# RGBM-02.net
KiCad netlist of a schematic drawn in Altium Designer
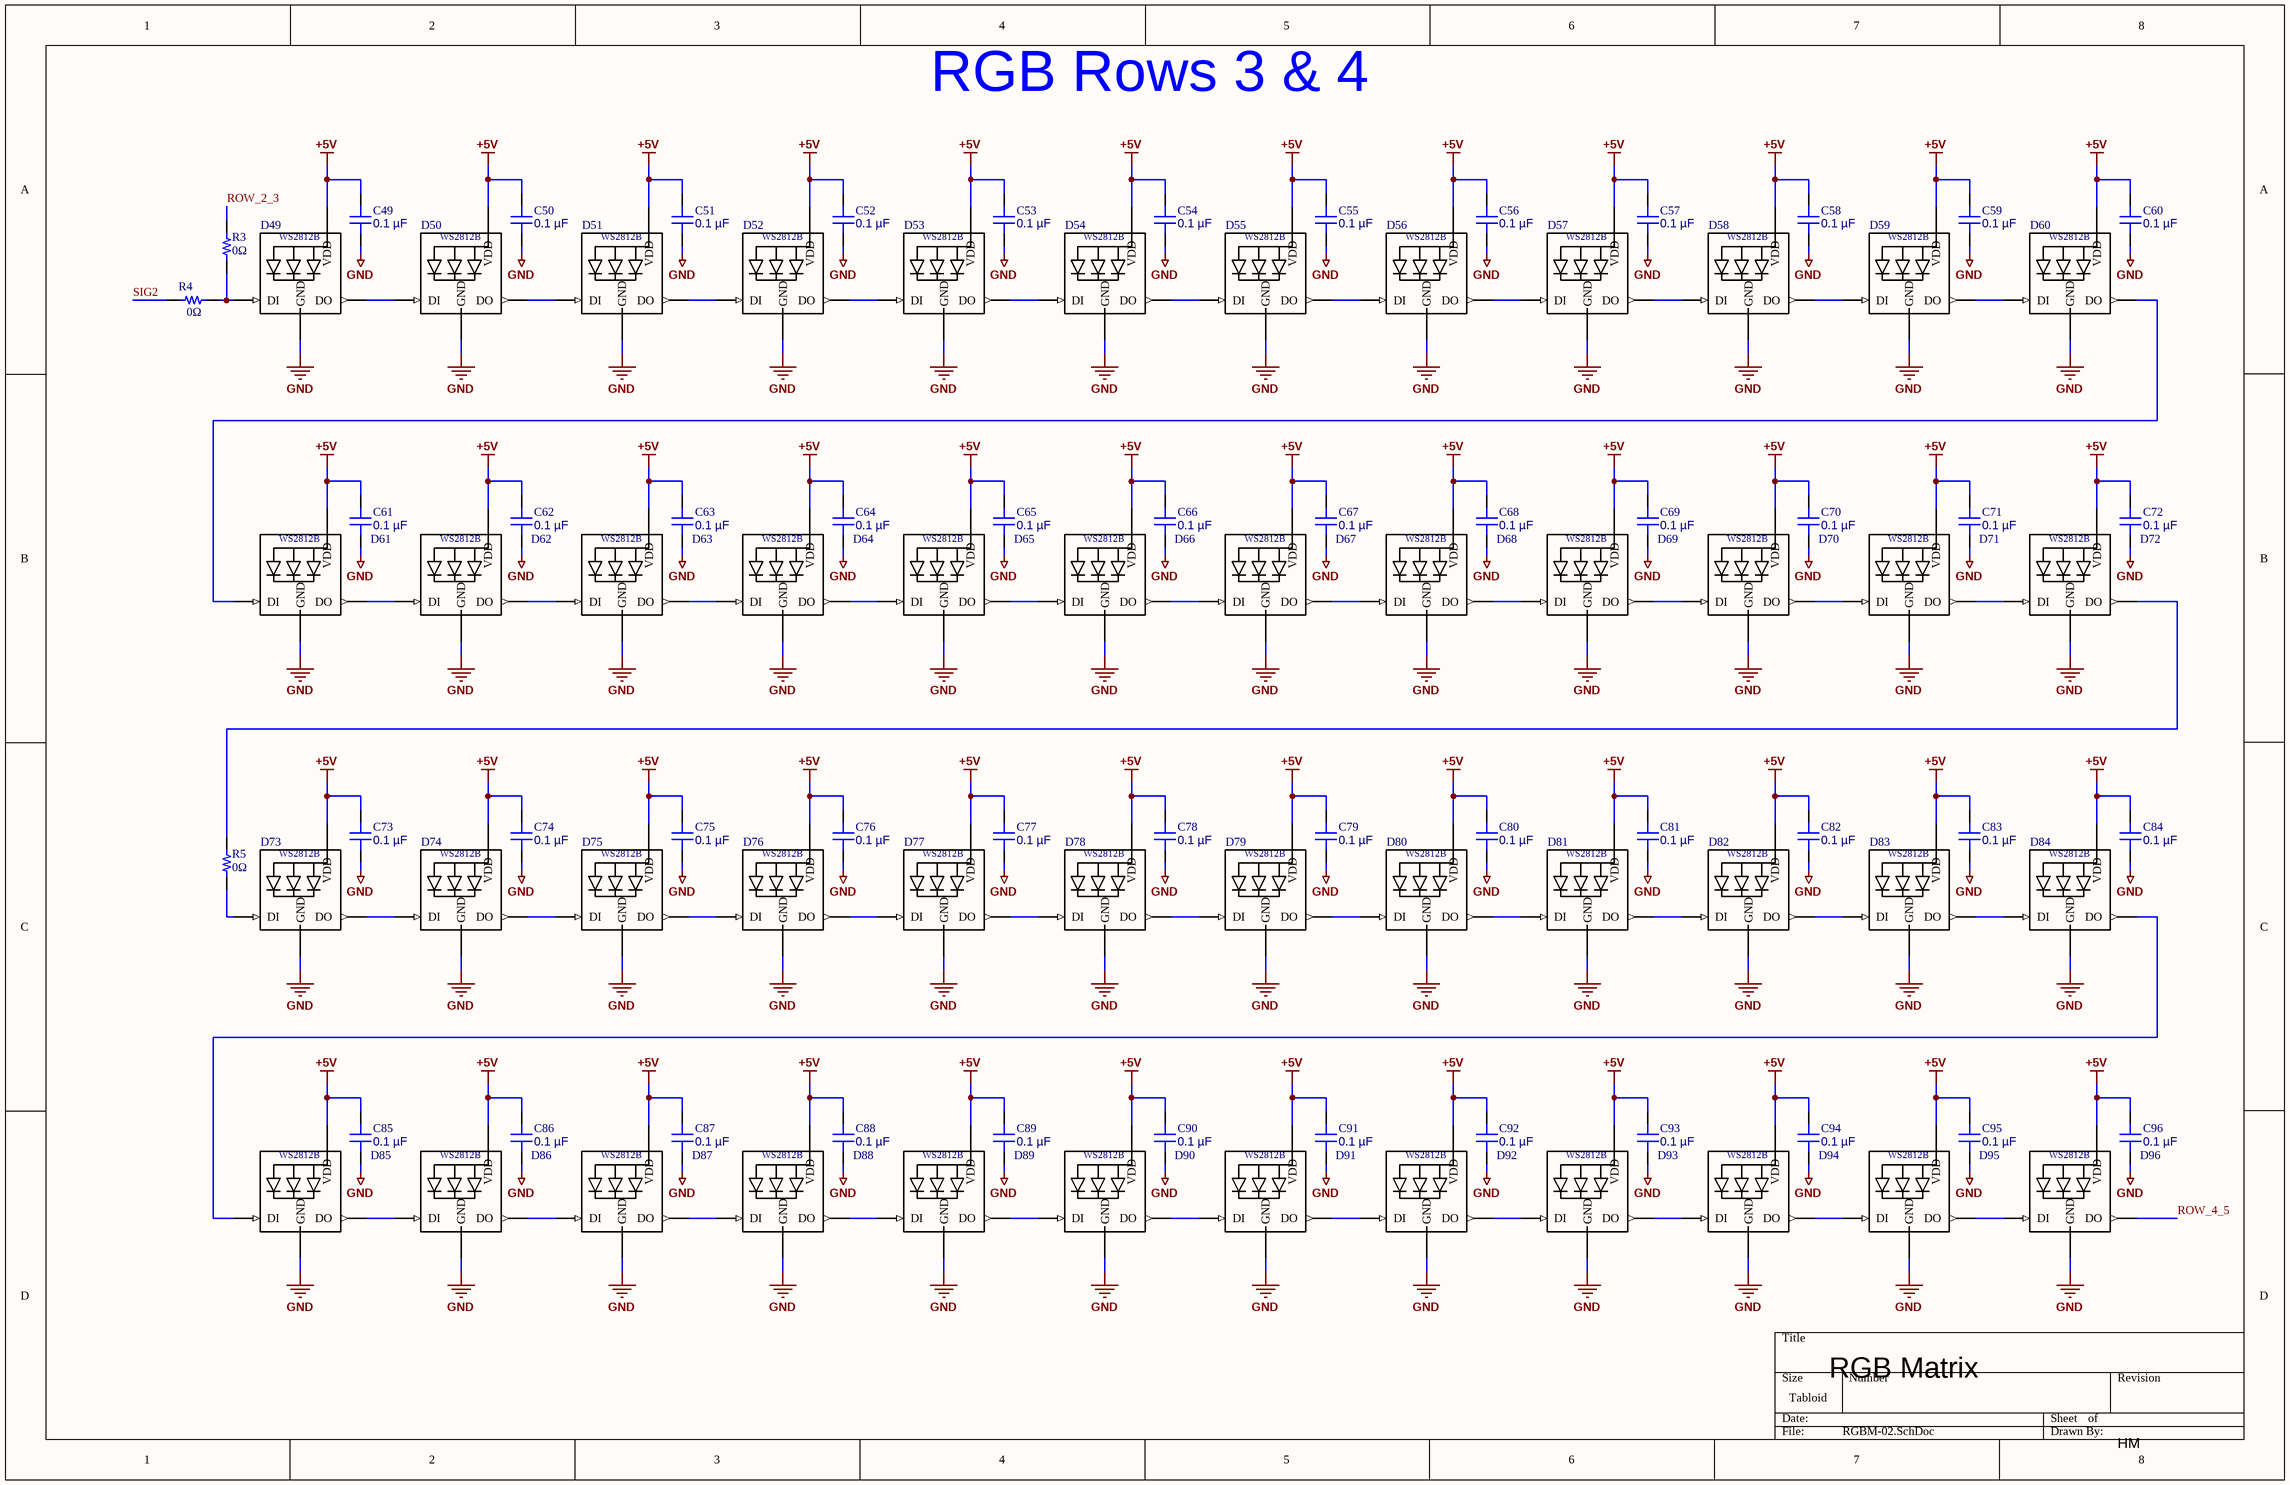
[diagram p0: RGBM-02.SchDoc]

(export (version "E")
  (design (tool "Eeschema 10.0.6"))
  (components
    (comp (ref "C49")
      (value "0.1 µF")
      (footprint "CAP 0603_1608")
      (description "CAP CER 0.1UF 50V X7R 0603")
      (fields
        (field (name "PART NUMBER") "C0603C104K5RAC7411")
        (field (name "CAPACITANCE") "0.1 µF")
        (field (name "MANUFACTURER") "KEMET")
      )
      (libsource (lib "Celestial Altium Library - altium_library") (part "Capacitor"))
    )
    (comp (ref "C50")
      (value "0.1 µF")
      (footprint "CAP 0603_1608")
      (description "CAP CER 0.1UF 50V X7R 0603")
      (fields
        (field (name "PART NUMBER") "C0603C104K5RAC7411")
        (field (name "CAPACITANCE") "0.1 µF")
        (field (name "MANUFACTURER") "KEMET")
      )
      (libsource (lib "Celestial Altium Library - altium_library") (part "Capacitor"))
    )
    (comp (ref "C51")
      (value "0.1 µF")
      (footprint "CAP 0603_1608")
      (description "CAP CER 0.1UF 50V X7R 0603")
      (fields
        (field (name "PART NUMBER") "C0603C104K5RAC7411")
        (field (name "CAPACITANCE") "0.1 µF")
        (field (name "MANUFACTURER") "KEMET")
      )
      (libsource (lib "Celestial Altium Library - altium_library") (part "Capacitor"))
    )
    (comp (ref "C52")
      (value "0.1 µF")
      (footprint "CAP 0603_1608")
      (description "CAP CER 0.1UF 50V X7R 0603")
      (fields
        (field (name "PART NUMBER") "C0603C104K5RAC7411")
        (field (name "CAPACITANCE") "0.1 µF")
        (field (name "MANUFACTURER") "KEMET")
      )
      (libsource (lib "Celestial Altium Library - altium_library") (part "Capacitor"))
    )
    (comp (ref "C53")
      (value "0.1 µF")
      (footprint "CAP 0603_1608")
      (description "CAP CER 0.1UF 50V X7R 0603")
      (fields
        (field (name "PART NUMBER") "C0603C104K5RAC7411")
        (field (name "CAPACITANCE") "0.1 µF")
        (field (name "MANUFACTURER") "KEMET")
      )
      (libsource (lib "Celestial Altium Library - altium_library") (part "Capacitor"))
    )
    (comp (ref "C54")
      (value "0.1 µF")
      (footprint "CAP 0603_1608")
      (description "CAP CER 0.1UF 50V X7R 0603")
      (fields
        (field (name "PART NUMBER") "C0603C104K5RAC7411")
        (field (name "CAPACITANCE") "0.1 µF")
        (field (name "MANUFACTURER") "KEMET")
      )
      (libsource (lib "Celestial Altium Library - altium_library") (part "Capacitor"))
    )
    (comp (ref "C55")
      (value "0.1 µF")
      (footprint "CAP 0603_1608")
      (description "CAP CER 0.1UF 50V X7R 0603")
      (fields
        (field (name "PART NUMBER") "C0603C104K5RAC7411")
        (field (name "CAPACITANCE") "0.1 µF")
        (field (name "MANUFACTURER") "KEMET")
      )
      (libsource (lib "Celestial Altium Library - altium_library") (part "Capacitor"))
    )
    (comp (ref "C56")
      (value "0.1 µF")
      (footprint "CAP 0603_1608")
      (description "CAP CER 0.1UF 50V X7R 0603")
      (fields
        (field (name "PART NUMBER") "C0603C104K5RAC7411")
        (field (name "CAPACITANCE") "0.1 µF")
        (field (name "MANUFACTURER") "KEMET")
      )
      (libsource (lib "Celestial Altium Library - altium_library") (part "Capacitor"))
    )
    (comp (ref "C57")
      (value "0.1 µF")
      (footprint "CAP 0603_1608")
      (description "CAP CER 0.1UF 50V X7R 0603")
      (fields
        (field (name "PART NUMBER") "C0603C104K5RAC7411")
        (field (name "CAPACITANCE") "0.1 µF")
        (field (name "MANUFACTURER") "KEMET")
      )
      (libsource (lib "Celestial Altium Library - altium_library") (part "Capacitor"))
    )
    (comp (ref "C58")
      (value "0.1 µF")
      (footprint "CAP 0603_1608")
      (description "CAP CER 0.1UF 50V X7R 0603")
      (fields
        (field (name "PART NUMBER") "C0603C104K5RAC7411")
        (field (name "CAPACITANCE") "0.1 µF")
        (field (name "MANUFACTURER") "KEMET")
      )
      (libsource (lib "Celestial Altium Library - altium_library") (part "Capacitor"))
    )
    (comp (ref "C59")
      (value "0.1 µF")
      (footprint "CAP 0603_1608")
      (description "CAP CER 0.1UF 50V X7R 0603")
      (fields
        (field (name "PART NUMBER") "C0603C104K5RAC7411")
        (field (name "CAPACITANCE") "0.1 µF")
        (field (name "MANUFACTURER") "KEMET")
      )
      (libsource (lib "Celestial Altium Library - altium_library") (part "Capacitor"))
    )
    (comp (ref "C60")
      (value "0.1 µF")
      (footprint "CAP 0603_1608")
      (description "CAP CER 0.1UF 50V X7R 0603")
      (fields
        (field (name "PART NUMBER") "C0603C104K5RAC7411")
        (field (name "CAPACITANCE") "0.1 µF")
        (field (name "MANUFACTURER") "KEMET")
      )
      (libsource (lib "Celestial Altium Library - altium_library") (part "Capacitor"))
    )
    (comp (ref "C61")
      (value "0.1 µF")
      (footprint "CAP 0603_1608")
      (description "CAP CER 0.1UF 50V X7R 0603")
      (fields
        (field (name "PART NUMBER") "C0603C104K5RAC7411")
        (field (name "CAPACITANCE") "0.1 µF")
        (field (name "MANUFACTURER") "KEMET")
      )
      (libsource (lib "Celestial Altium Library - altium_library") (part "Capacitor"))
    )
    (comp (ref "C62")
      (value "0.1 µF")
      (footprint "CAP 0603_1608")
      (description "CAP CER 0.1UF 50V X7R 0603")
      (fields
        (field (name "PART NUMBER") "C0603C104K5RAC7411")
        (field (name "CAPACITANCE") "0.1 µF")
        (field (name "MANUFACTURER") "KEMET")
      )
      (libsource (lib "Celestial Altium Library - altium_library") (part "Capacitor"))
    )
    (comp (ref "C63")
      (value "0.1 µF")
      (footprint "CAP 0603_1608")
      (description "CAP CER 0.1UF 50V X7R 0603")
      (fields
        (field (name "PART NUMBER") "C0603C104K5RAC7411")
        (field (name "CAPACITANCE") "0.1 µF")
        (field (name "MANUFACTURER") "KEMET")
      )
      (libsource (lib "Celestial Altium Library - altium_library") (part "Capacitor"))
    )
    (comp (ref "C64")
      (value "0.1 µF")
      (footprint "CAP 0603_1608")
      (description "CAP CER 0.1UF 50V X7R 0603")
      (fields
        (field (name "PART NUMBER") "C0603C104K5RAC7411")
        (field (name "CAPACITANCE") "0.1 µF")
        (field (name "MANUFACTURER") "KEMET")
      )
      (libsource (lib "Celestial Altium Library - altium_library") (part "Capacitor"))
    )
    (comp (ref "C65")
      (value "0.1 µF")
      (footprint "CAP 0603_1608")
      (description "CAP CER 0.1UF 50V X7R 0603")
      (fields
        (field (name "PART NUMBER") "C0603C104K5RAC7411")
        (field (name "CAPACITANCE") "0.1 µF")
        (field (name "MANUFACTURER") "KEMET")
      )
      (libsource (lib "Celestial Altium Library - altium_library") (part "Capacitor"))
    )
    (comp (ref "C66")
      (value "0.1 µF")
      (footprint "CAP 0603_1608")
      (description "CAP CER 0.1UF 50V X7R 0603")
      (fields
        (field (name "PART NUMBER") "C0603C104K5RAC7411")
        (field (name "CAPACITANCE") "0.1 µF")
        (field (name "MANUFACTURER") "KEMET")
      )
      (libsource (lib "Celestial Altium Library - altium_library") (part "Capacitor"))
    )
    (comp (ref "C67")
      (value "0.1 µF")
      (footprint "CAP 0603_1608")
      (description "CAP CER 0.1UF 50V X7R 0603")
      (fields
        (field (name "PART NUMBER") "C0603C104K5RAC7411")
        (field (name "CAPACITANCE") "0.1 µF")
        (field (name "MANUFACTURER") "KEMET")
      )
      (libsource (lib "Celestial Altium Library - altium_library") (part "Capacitor"))
    )
    (comp (ref "C68")
      (value "0.1 µF")
      (footprint "CAP 0603_1608")
      (description "CAP CER 0.1UF 50V X7R 0603")
      (fields
        (field (name "PART NUMBER") "C0603C104K5RAC7411")
        (field (name "CAPACITANCE") "0.1 µF")
        (field (name "MANUFACTURER") "KEMET")
      )
      (libsource (lib "Celestial Altium Library - altium_library") (part "Capacitor"))
    )
    (comp (ref "C69")
      (value "0.1 µF")
      (footprint "CAP 0603_1608")
      (description "CAP CER 0.1UF 50V X7R 0603")
      (fields
        (field (name "PART NUMBER") "C0603C104K5RAC7411")
        (field (name "CAPACITANCE") "0.1 µF")
        (field (name "MANUFACTURER") "KEMET")
      )
      (libsource (lib "Celestial Altium Library - altium_library") (part "Capacitor"))
    )
    (comp (ref "C70")
      (value "0.1 µF")
      (footprint "CAP 0603_1608")
      (description "CAP CER 0.1UF 50V X7R 0603")
      (fields
        (field (name "PART NUMBER") "C0603C104K5RAC7411")
        (field (name "CAPACITANCE") "0.1 µF")
        (field (name "MANUFACTURER") "KEMET")
      )
      (libsource (lib "Celestial Altium Library - altium_library") (part "Capacitor"))
    )
    (comp (ref "C71")
      (value "0.1 µF")
      (footprint "CAP 0603_1608")
      (description "CAP CER 0.1UF 50V X7R 0603")
      (fields
        (field (name "PART NUMBER") "C0603C104K5RAC7411")
        (field (name "CAPACITANCE") "0.1 µF")
        (field (name "MANUFACTURER") "KEMET")
      )
      (libsource (lib "Celestial Altium Library - altium_library") (part "Capacitor"))
    )
    (comp (ref "C72")
      (value "0.1 µF")
      (footprint "CAP 0603_1608")
      (description "CAP CER 0.1UF 50V X7R 0603")
      (fields
        (field (name "PART NUMBER") "C0603C104K5RAC7411")
        (field (name "CAPACITANCE") "0.1 µF")
        (field (name "MANUFACTURER") "KEMET")
      )
      (libsource (lib "Celestial Altium Library - altium_library") (part "Capacitor"))
    )
    (comp (ref "C73")
      (value "0.1 µF")
      (footprint "CAP 0603_1608")
      (description "CAP CER 0.1UF 50V X7R 0603")
      (fields
        (field (name "PART NUMBER") "C0603C104K5RAC7411")
        (field (name "CAPACITANCE") "0.1 µF")
        (field (name "MANUFACTURER") "KEMET")
      )
      (libsource (lib "Celestial Altium Library - altium_library") (part "Capacitor"))
    )
    (comp (ref "C74")
      (value "0.1 µF")
      (footprint "CAP 0603_1608")
      (description "CAP CER 0.1UF 50V X7R 0603")
      (fields
        (field (name "PART NUMBER") "C0603C104K5RAC7411")
        (field (name "CAPACITANCE") "0.1 µF")
        (field (name "MANUFACTURER") "KEMET")
      )
      (libsource (lib "Celestial Altium Library - altium_library") (part "Capacitor"))
    )
    (comp (ref "C75")
      (value "0.1 µF")
      (footprint "CAP 0603_1608")
      (description "CAP CER 0.1UF 50V X7R 0603")
      (fields
        (field (name "PART NUMBER") "C0603C104K5RAC7411")
        (field (name "CAPACITANCE") "0.1 µF")
        (field (name "MANUFACTURER") "KEMET")
      )
      (libsource (lib "Celestial Altium Library - altium_library") (part "Capacitor"))
    )
    (comp (ref "C76")
      (value "0.1 µF")
      (footprint "CAP 0603_1608")
      (description "CAP CER 0.1UF 50V X7R 0603")
      (fields
        (field (name "PART NUMBER") "C0603C104K5RAC7411")
        (field (name "CAPACITANCE") "0.1 µF")
        (field (name "MANUFACTURER") "KEMET")
      )
      (libsource (lib "Celestial Altium Library - altium_library") (part "Capacitor"))
    )
    (comp (ref "C77")
      (value "0.1 µF")
      (footprint "CAP 0603_1608")
      (description "CAP CER 0.1UF 50V X7R 0603")
      (fields
        (field (name "PART NUMBER") "C0603C104K5RAC7411")
        (field (name "CAPACITANCE") "0.1 µF")
        (field (name "MANUFACTURER") "KEMET")
      )
      (libsource (lib "Celestial Altium Library - altium_library") (part "Capacitor"))
    )
    (comp (ref "C78")
      (value "0.1 µF")
      (footprint "CAP 0603_1608")
      (description "CAP CER 0.1UF 50V X7R 0603")
      (fields
        (field (name "PART NUMBER") "C0603C104K5RAC7411")
        (field (name "CAPACITANCE") "0.1 µF")
        (field (name "MANUFACTURER") "KEMET")
      )
      (libsource (lib "Celestial Altium Library - altium_library") (part "Capacitor"))
    )
    (comp (ref "C79")
      (value "0.1 µF")
      (footprint "CAP 0603_1608")
      (description "CAP CER 0.1UF 50V X7R 0603")
      (fields
        (field (name "PART NUMBER") "C0603C104K5RAC7411")
        (field (name "CAPACITANCE") "0.1 µF")
        (field (name "MANUFACTURER") "KEMET")
      )
      (libsource (lib "Celestial Altium Library - altium_library") (part "Capacitor"))
    )
    (comp (ref "C80")
      (value "0.1 µF")
      (footprint "CAP 0603_1608")
      (description "CAP CER 0.1UF 50V X7R 0603")
      (fields
        (field (name "PART NUMBER") "C0603C104K5RAC7411")
        (field (name "CAPACITANCE") "0.1 µF")
        (field (name "MANUFACTURER") "KEMET")
      )
      (libsource (lib "Celestial Altium Library - altium_library") (part "Capacitor"))
    )
    (comp (ref "C81")
      (value "0.1 µF")
      (footprint "CAP 0603_1608")
      (description "CAP CER 0.1UF 50V X7R 0603")
      (fields
        (field (name "PART NUMBER") "C0603C104K5RAC7411")
        (field (name "CAPACITANCE") "0.1 µF")
        (field (name "MANUFACTURER") "KEMET")
      )
      (libsource (lib "Celestial Altium Library - altium_library") (part "Capacitor"))
    )
    (comp (ref "C82")
      (value "0.1 µF")
      (footprint "CAP 0603_1608")
      (description "CAP CER 0.1UF 50V X7R 0603")
      (fields
        (field (name "PART NUMBER") "C0603C104K5RAC7411")
        (field (name "CAPACITANCE") "0.1 µF")
        (field (name "MANUFACTURER") "KEMET")
      )
      (libsource (lib "Celestial Altium Library - altium_library") (part "Capacitor"))
    )
    (comp (ref "C83")
      (value "0.1 µF")
      (footprint "CAP 0603_1608")
      (description "CAP CER 0.1UF 50V X7R 0603")
      (fields
        (field (name "PART NUMBER") "C0603C104K5RAC7411")
        (field (name "CAPACITANCE") "0.1 µF")
        (field (name "MANUFACTURER") "KEMET")
      )
      (libsource (lib "Celestial Altium Library - altium_library") (part "Capacitor"))
    )
    (comp (ref "C84")
      (value "0.1 µF")
      (footprint "CAP 0603_1608")
      (description "CAP CER 0.1UF 50V X7R 0603")
      (fields
        (field (name "PART NUMBER") "C0603C104K5RAC7411")
        (field (name "CAPACITANCE") "0.1 µF")
        (field (name "MANUFACTURER") "KEMET")
      )
      (libsource (lib "Celestial Altium Library - altium_library") (part "Capacitor"))
    )
    (comp (ref "C85")
      (value "0.1 µF")
      (footprint "CAP 0603_1608")
      (description "CAP CER 0.1UF 50V X7R 0603")
      (fields
        (field (name "PART NUMBER") "C0603C104K5RAC7411")
        (field (name "CAPACITANCE") "0.1 µF")
        (field (name "MANUFACTURER") "KEMET")
      )
      (libsource (lib "Celestial Altium Library - altium_library") (part "Capacitor"))
    )
    (comp (ref "C86")
      (value "0.1 µF")
      (footprint "CAP 0603_1608")
      (description "CAP CER 0.1UF 50V X7R 0603")
      (fields
        (field (name "PART NUMBER") "C0603C104K5RAC7411")
        (field (name "CAPACITANCE") "0.1 µF")
        (field (name "MANUFACTURER") "KEMET")
      )
      (libsource (lib "Celestial Altium Library - altium_library") (part "Capacitor"))
    )
    (comp (ref "C87")
      (value "0.1 µF")
      (footprint "CAP 0603_1608")
      (description "CAP CER 0.1UF 50V X7R 0603")
      (fields
        (field (name "PART NUMBER") "C0603C104K5RAC7411")
        (field (name "CAPACITANCE") "0.1 µF")
        (field (name "MANUFACTURER") "KEMET")
      )
      (libsource (lib "Celestial Altium Library - altium_library") (part "Capacitor"))
    )
    (comp (ref "C88")
      (value "0.1 µF")
      (footprint "CAP 0603_1608")
      (description "CAP CER 0.1UF 50V X7R 0603")
      (fields
        (field (name "PART NUMBER") "C0603C104K5RAC7411")
        (field (name "CAPACITANCE") "0.1 µF")
        (field (name "MANUFACTURER") "KEMET")
      )
      (libsource (lib "Celestial Altium Library - altium_library") (part "Capacitor"))
    )
    (comp (ref "C89")
      (value "0.1 µF")
      (footprint "CAP 0603_1608")
      (description "CAP CER 0.1UF 50V X7R 0603")
      (fields
        (field (name "PART NUMBER") "C0603C104K5RAC7411")
        (field (name "CAPACITANCE") "0.1 µF")
        (field (name "MANUFACTURER") "KEMET")
      )
      (libsource (lib "Celestial Altium Library - altium_library") (part "Capacitor"))
    )
    (comp (ref "C90")
      (value "0.1 µF")
      (footprint "CAP 0603_1608")
      (description "CAP CER 0.1UF 50V X7R 0603")
      (fields
        (field (name "PART NUMBER") "C0603C104K5RAC7411")
        (field (name "CAPACITANCE") "0.1 µF")
        (field (name "MANUFACTURER") "KEMET")
      )
      (libsource (lib "Celestial Altium Library - altium_library") (part "Capacitor"))
    )
    (comp (ref "C91")
      (value "0.1 µF")
      (footprint "CAP 0603_1608")
      (description "CAP CER 0.1UF 50V X7R 0603")
      (fields
        (field (name "PART NUMBER") "C0603C104K5RAC7411")
        (field (name "CAPACITANCE") "0.1 µF")
        (field (name "MANUFACTURER") "KEMET")
      )
      (libsource (lib "Celestial Altium Library - altium_library") (part "Capacitor"))
    )
    (comp (ref "C92")
      (value "0.1 µF")
      (footprint "CAP 0603_1608")
      (description "CAP CER 0.1UF 50V X7R 0603")
      (fields
        (field (name "PART NUMBER") "C0603C104K5RAC7411")
        (field (name "CAPACITANCE") "0.1 µF")
        (field (name "MANUFACTURER") "KEMET")
      )
      (libsource (lib "Celestial Altium Library - altium_library") (part "Capacitor"))
    )
    (comp (ref "C93")
      (value "0.1 µF")
      (footprint "CAP 0603_1608")
      (description "CAP CER 0.1UF 50V X7R 0603")
      (fields
        (field (name "PART NUMBER") "C0603C104K5RAC7411")
        (field (name "CAPACITANCE") "0.1 µF")
        (field (name "MANUFACTURER") "KEMET")
      )
      (libsource (lib "Celestial Altium Library - altium_library") (part "Capacitor"))
    )
    (comp (ref "C94")
      (value "0.1 µF")
      (footprint "CAP 0603_1608")
      (description "CAP CER 0.1UF 50V X7R 0603")
      (fields
        (field (name "PART NUMBER") "C0603C104K5RAC7411")
        (field (name "CAPACITANCE") "0.1 µF")
        (field (name "MANUFACTURER") "KEMET")
      )
      (libsource (lib "Celestial Altium Library - altium_library") (part "Capacitor"))
    )
    (comp (ref "C95")
      (value "0.1 µF")
      (footprint "CAP 0603_1608")
      (description "CAP CER 0.1UF 50V X7R 0603")
      (fields
        (field (name "PART NUMBER") "C0603C104K5RAC7411")
        (field (name "CAPACITANCE") "0.1 µF")
        (field (name "MANUFACTURER") "KEMET")
      )
      (libsource (lib "Celestial Altium Library - altium_library") (part "Capacitor"))
    )
    (comp (ref "C96")
      (value "0.1 µF")
      (footprint "CAP 0603_1608")
      (description "CAP CER 0.1UF 50V X7R 0603")
      (fields
        (field (name "PART NUMBER") "C0603C104K5RAC7411")
        (field (name "CAPACITANCE") "0.1 µF")
        (field (name "MANUFACTURER") "KEMET")
      )
      (libsource (lib "Celestial Altium Library - altium_library") (part "Capacitor"))
    )
    (comp (ref "D49")
      (value "WS2812B")
      (footprint "*WS2812B_WS2812B(Primary)")
      (description "Intelligent control LED integrated light source")
      (fields (field (name "MF") "Worldsemi"))
      (libsource (lib "WS2812B") (part "WS2812B"))
    )
    (comp (ref "D50")
      (value "WS2812B")
      (footprint "*WS2812B_WS2812B(Primary)")
      (description "Intelligent control LED integrated light source")
      (fields (field (name "MF") "Worldsemi"))
      (libsource (lib "WS2812B") (part "WS2812B"))
    )
    (comp (ref "D51")
      (value "WS2812B")
      (footprint "*WS2812B_WS2812B(Primary)")
      (description "Intelligent control LED integrated light source")
      (fields (field (name "MF") "Worldsemi"))
      (libsource (lib "WS2812B") (part "WS2812B"))
    )
    (comp (ref "D52")
      (value "WS2812B")
      (footprint "*WS2812B_WS2812B(Primary)")
      (description "Intelligent control LED integrated light source")
      (fields (field (name "MF") "Worldsemi"))
      (libsource (lib "WS2812B") (part "WS2812B"))
    )
    (comp (ref "D53")
      (value "WS2812B")
      (footprint "*WS2812B_WS2812B(Primary)")
      (description "Intelligent control LED integrated light source")
      (fields (field (name "MF") "Worldsemi"))
      (libsource (lib "WS2812B") (part "WS2812B"))
    )
    (comp (ref "D54")
      (value "WS2812B")
      (footprint "*WS2812B_WS2812B(Primary)")
      (description "Intelligent control LED integrated light source")
      (fields (field (name "MF") "Worldsemi"))
      (libsource (lib "WS2812B") (part "WS2812B"))
    )
    (comp (ref "D55")
      (value "WS2812B")
      (footprint "*WS2812B_WS2812B(Primary)")
      (description "Intelligent control LED integrated light source")
      (fields (field (name "MF") "Worldsemi"))
      (libsource (lib "WS2812B") (part "WS2812B"))
    )
    (comp (ref "D56")
      (value "WS2812B")
      (footprint "*WS2812B_WS2812B(Primary)")
      (description "Intelligent control LED integrated light source")
      (fields (field (name "MF") "Worldsemi"))
      (libsource (lib "WS2812B") (part "WS2812B"))
    )
    (comp (ref "D57")
      (value "WS2812B")
      (footprint "*WS2812B_WS2812B(Primary)")
      (description "Intelligent control LED integrated light source")
      (fields (field (name "MF") "Worldsemi"))
      (libsource (lib "WS2812B") (part "WS2812B"))
    )
    (comp (ref "D58")
      (value "WS2812B")
      (footprint "*WS2812B_WS2812B(Primary)")
      (description "Intelligent control LED integrated light source")
      (fields (field (name "MF") "Worldsemi"))
      (libsource (lib "WS2812B") (part "WS2812B"))
    )
    (comp (ref "D59")
      (value "WS2812B")
      (footprint "*WS2812B_WS2812B(Primary)")
      (description "Intelligent control LED integrated light source")
      (fields (field (name "MF") "Worldsemi"))
      (libsource (lib "WS2812B") (part "WS2812B"))
    )
    (comp (ref "D60")
      (value "WS2812B")
      (footprint "*WS2812B_WS2812B(Primary)")
      (description "Intelligent control LED integrated light source")
      (fields (field (name "MF") "Worldsemi"))
      (libsource (lib "WS2812B") (part "WS2812B"))
    )
    (comp (ref "D61")
      (value "WS2812B")
      (footprint "*WS2812B_WS2812B(Primary)")
      (description "Intelligent control LED integrated light source")
      (fields (field (name "MF") "Worldsemi"))
      (libsource (lib "WS2812B") (part "WS2812B"))
    )
    (comp (ref "D62")
      (value "WS2812B")
      (footprint "*WS2812B_WS2812B(Primary)")
      (description "Intelligent control LED integrated light source")
      (fields (field (name "MF") "Worldsemi"))
      (libsource (lib "WS2812B") (part "WS2812B"))
    )
    (comp (ref "D63")
      (value "WS2812B")
      (footprint "*WS2812B_WS2812B(Primary)")
      (description "Intelligent control LED integrated light source")
      (fields (field (name "MF") "Worldsemi"))
      (libsource (lib "WS2812B") (part "WS2812B"))
    )
    (comp (ref "D64")
      (value "WS2812B")
      (footprint "*WS2812B_WS2812B(Primary)")
      (description "Intelligent control LED integrated light source")
      (fields (field (name "MF") "Worldsemi"))
      (libsource (lib "WS2812B") (part "WS2812B"))
    )
    (comp (ref "D65")
      (value "WS2812B")
      (footprint "*WS2812B_WS2812B(Primary)")
      (description "Intelligent control LED integrated light source")
      (fields (field (name "MF") "Worldsemi"))
      (libsource (lib "WS2812B") (part "WS2812B"))
    )
    (comp (ref "D66")
      (value "WS2812B")
      (footprint "*WS2812B_WS2812B(Primary)")
      (description "Intelligent control LED integrated light source")
      (fields (field (name "MF") "Worldsemi"))
      (libsource (lib "WS2812B") (part "WS2812B"))
    )
    (comp (ref "D67")
      (value "WS2812B")
      (footprint "*WS2812B_WS2812B(Primary)")
      (description "Intelligent control LED integrated light source")
      (fields (field (name "MF") "Worldsemi"))
      (libsource (lib "WS2812B") (part "WS2812B"))
    )
    (comp (ref "D68")
      (value "WS2812B")
      (footprint "*WS2812B_WS2812B(Primary)")
      (description "Intelligent control LED integrated light source")
      (fields (field (name "MF") "Worldsemi"))
      (libsource (lib "WS2812B") (part "WS2812B"))
    )
    (comp (ref "D69")
      (value "WS2812B")
      (footprint "*WS2812B_WS2812B(Primary)")
      (description "Intelligent control LED integrated light source")
      (fields (field (name "MF") "Worldsemi"))
      (libsource (lib "WS2812B") (part "WS2812B"))
    )
    (comp (ref "D70")
      (value "WS2812B")
      (footprint "*WS2812B_WS2812B(Primary)")
      (description "Intelligent control LED integrated light source")
      (fields (field (name "MF") "Worldsemi"))
      (libsource (lib "WS2812B") (part "WS2812B"))
    )
    (comp (ref "D71")
      (value "WS2812B")
      (footprint "*WS2812B_WS2812B(Primary)")
      (description "Intelligent control LED integrated light source")
      (fields (field (name "MF") "Worldsemi"))
      (libsource (lib "WS2812B") (part "WS2812B"))
    )
    (comp (ref "D72")
      (value "WS2812B")
      (footprint "*WS2812B_WS2812B(Primary)")
      (description "Intelligent control LED integrated light source")
      (fields (field (name "MF") "Worldsemi"))
      (libsource (lib "WS2812B") (part "WS2812B"))
    )
    (comp (ref "D73")
      (value "WS2812B")
      (footprint "*WS2812B_WS2812B(Primary)")
      (description "Intelligent control LED integrated light source")
      (fields (field (name "MF") "Worldsemi"))
      (libsource (lib "WS2812B") (part "WS2812B"))
    )
    (comp (ref "D74")
      (value "WS2812B")
      (footprint "*WS2812B_WS2812B(Primary)")
      (description "Intelligent control LED integrated light source")
      (fields (field (name "MF") "Worldsemi"))
      (libsource (lib "WS2812B") (part "WS2812B"))
    )
    (comp (ref "D75")
      (value "WS2812B")
      (footprint "*WS2812B_WS2812B(Primary)")
      (description "Intelligent control LED integrated light source")
      (fields (field (name "MF") "Worldsemi"))
      (libsource (lib "WS2812B") (part "WS2812B"))
    )
    (comp (ref "D76")
      (value "WS2812B")
      (footprint "*WS2812B_WS2812B(Primary)")
      (description "Intelligent control LED integrated light source")
      (fields (field (name "MF") "Worldsemi"))
      (libsource (lib "WS2812B") (part "WS2812B"))
    )
    (comp (ref "D77")
      (value "WS2812B")
      (footprint "*WS2812B_WS2812B(Primary)")
      (description "Intelligent control LED integrated light source")
      (fields (field (name "MF") "Worldsemi"))
      (libsource (lib "WS2812B") (part "WS2812B"))
    )
    (comp (ref "D78")
      (value "WS2812B")
      (footprint "*WS2812B_WS2812B(Primary)")
      (description "Intelligent control LED integrated light source")
      (fields (field (name "MF") "Worldsemi"))
      (libsource (lib "WS2812B") (part "WS2812B"))
    )
    (comp (ref "D79")
      (value "WS2812B")
      (footprint "*WS2812B_WS2812B(Primary)")
      (description "Intelligent control LED integrated light source")
      (fields (field (name "MF") "Worldsemi"))
      (libsource (lib "WS2812B") (part "WS2812B"))
    )
    (comp (ref "D80")
      (value "WS2812B")
      (footprint "*WS2812B_WS2812B(Primary)")
      (description "Intelligent control LED integrated light source")
      (fields (field (name "MF") "Worldsemi"))
      (libsource (lib "WS2812B") (part "WS2812B"))
    )
    (comp (ref "D81")
      (value "WS2812B")
      (footprint "*WS2812B_WS2812B(Primary)")
      (description "Intelligent control LED integrated light source")
      (fields (field (name "MF") "Worldsemi"))
      (libsource (lib "WS2812B") (part "WS2812B"))
    )
    (comp (ref "D82")
      (value "WS2812B")
      (footprint "*WS2812B_WS2812B(Primary)")
      (description "Intelligent control LED integrated light source")
      (fields (field (name "MF") "Worldsemi"))
      (libsource (lib "WS2812B") (part "WS2812B"))
    )
    (comp (ref "D83")
      (value "WS2812B")
      (footprint "*WS2812B_WS2812B(Primary)")
      (description "Intelligent control LED integrated light source")
      (fields (field (name "MF") "Worldsemi"))
      (libsource (lib "WS2812B") (part "WS2812B"))
    )
    (comp (ref "D84")
      (value "WS2812B")
      (footprint "*WS2812B_WS2812B(Primary)")
      (description "Intelligent control LED integrated light source")
      (fields (field (name "MF") "Worldsemi"))
      (libsource (lib "WS2812B") (part "WS2812B"))
    )
    (comp (ref "D85")
      (value "WS2812B")
      (footprint "*WS2812B_WS2812B(Primary)")
      (description "Intelligent control LED integrated light source")
      (fields (field (name "MF") "Worldsemi"))
      (libsource (lib "WS2812B") (part "WS2812B"))
    )
    (comp (ref "D86")
      (value "WS2812B")
      (footprint "*WS2812B_WS2812B(Primary)")
      (description "Intelligent control LED integrated light source")
      (fields (field (name "MF") "Worldsemi"))
      (libsource (lib "WS2812B") (part "WS2812B"))
    )
    (comp (ref "D87")
      (value "WS2812B")
      (footprint "*WS2812B_WS2812B(Primary)")
      (description "Intelligent control LED integrated light source")
      (fields (field (name "MF") "Worldsemi"))
      (libsource (lib "WS2812B") (part "WS2812B"))
    )
    (comp (ref "D88")
      (value "WS2812B")
      (footprint "*WS2812B_WS2812B(Primary)")
      (description "Intelligent control LED integrated light source")
      (fields (field (name "MF") "Worldsemi"))
      (libsource (lib "WS2812B") (part "WS2812B"))
    )
    (comp (ref "D89")
      (value "WS2812B")
      (footprint "*WS2812B_WS2812B(Primary)")
      (description "Intelligent control LED integrated light source")
      (fields (field (name "MF") "Worldsemi"))
      (libsource (lib "WS2812B") (part "WS2812B"))
    )
    (comp (ref "D90")
      (value "WS2812B")
      (footprint "*WS2812B_WS2812B(Primary)")
      (description "Intelligent control LED integrated light source")
      (fields (field (name "MF") "Worldsemi"))
      (libsource (lib "WS2812B") (part "WS2812B"))
    )
    (comp (ref "D91")
      (value "WS2812B")
      (footprint "*WS2812B_WS2812B(Primary)")
      (description "Intelligent control LED integrated light source")
      (fields (field (name "MF") "Worldsemi"))
      (libsource (lib "WS2812B") (part "WS2812B"))
    )
    (comp (ref "D92")
      (value "WS2812B")
      (footprint "*WS2812B_WS2812B(Primary)")
      (description "Intelligent control LED integrated light source")
      (fields (field (name "MF") "Worldsemi"))
      (libsource (lib "WS2812B") (part "WS2812B"))
    )
    (comp (ref "D93")
      (value "WS2812B")
      (footprint "*WS2812B_WS2812B(Primary)")
      (description "Intelligent control LED integrated light source")
      (fields (field (name "MF") "Worldsemi"))
      (libsource (lib "WS2812B") (part "WS2812B"))
    )
    (comp (ref "D94")
      (value "WS2812B")
      (footprint "*WS2812B_WS2812B(Primary)")
      (description "Intelligent control LED integrated light source")
      (fields (field (name "MF") "Worldsemi"))
      (libsource (lib "WS2812B") (part "WS2812B"))
    )
    (comp (ref "D95")
      (value "WS2812B")
      (footprint "*WS2812B_WS2812B(Primary)")
      (description "Intelligent control LED integrated light source")
      (fields (field (name "MF") "Worldsemi"))
      (libsource (lib "WS2812B") (part "WS2812B"))
    )
    (comp (ref "D96")
      (value "WS2812B")
      (footprint "*WS2812B_WS2812B(Primary)")
      (description "Intelligent control LED integrated light source")
      (fields (field (name "MF") "Worldsemi"))
      (libsource (lib "WS2812B") (part "WS2812B"))
    )
    (comp (ref "R3")
      (value "0Ω")
      (footprint "RES 0603_1608")
      (description "RES SMD 0 OHM JUMPER 0603")
      (fields (field (name "PART NUMBER") "YJP1608-R001") (field (name "MANUFACTURER") "Susumu"))
      (libsource (lib "Celestial Altium Library - altium_library") (part "Resistor"))
    )
    (comp (ref "R4")
      (value "0Ω")
      (footprint "RES 0603_1608")
      (description "RES SMD 0 OHM JUMPER 0603")
      (fields (field (name "PART NUMBER") "YJP1608-R001") (field (name "MANUFACTURER") "Susumu"))
      (libsource (lib "Celestial Altium Library - altium_library") (part "Resistor"))
    )
    (comp (ref "R5")
      (value "0Ω")
      (footprint "RES 0603_1608")
      (description "RES SMD 0 OHM JUMPER 0603")
      (fields (field (name "PART NUMBER") "YJP1608-R001") (field (name "MANUFACTURER") "Susumu"))
      (libsource (lib "Celestial Altium Library - altium_library") (part "Resistor"))
    )
  )
  (nets
    (net (code "1") (name "+5V") (class "Default")
      (node (ref "C49") (pin "2") (pinfunction "2_2") (pintype "passive"))
      (node (ref "C50") (pin "2") (pinfunction "2_2") (pintype "passive"))
      (node (ref "C51") (pin "2") (pinfunction "2_2") (pintype "passive"))
      (node (ref "C52") (pin "2") (pinfunction "2_2") (pintype "passive"))
      (node (ref "C53") (pin "2") (pinfunction "2_2") (pintype "passive"))
      (node (ref "C54") (pin "2") (pinfunction "2_2") (pintype "passive"))
      (node (ref "C55") (pin "2") (pinfunction "2_2") (pintype "passive"))
      (node (ref "C56") (pin "2") (pinfunction "2_2") (pintype "passive"))
      (node (ref "C57") (pin "2") (pinfunction "2_2") (pintype "passive"))
      (node (ref "C58") (pin "2") (pinfunction "2_2") (pintype "passive"))
      (node (ref "C59") (pin "2") (pinfunction "2_2") (pintype "passive"))
      (node (ref "C60") (pin "2") (pinfunction "2_2") (pintype "passive"))
      (node (ref "C61") (pin "2") (pinfunction "2_2") (pintype "passive"))
      (node (ref "C62") (pin "2") (pinfunction "2_2") (pintype "passive"))
      (node (ref "C63") (pin "2") (pinfunction "2_2") (pintype "passive"))
      (node (ref "C64") (pin "2") (pinfunction "2_2") (pintype "passive"))
      (node (ref "C65") (pin "2") (pinfunction "2_2") (pintype "passive"))
      (node (ref "C66") (pin "2") (pinfunction "2_2") (pintype "passive"))
      (node (ref "C67") (pin "2") (pinfunction "2_2") (pintype "passive"))
      (node (ref "C68") (pin "2") (pinfunction "2_2") (pintype "passive"))
      (node (ref "C69") (pin "2") (pinfunction "2_2") (pintype "passive"))
      (node (ref "C70") (pin "2") (pinfunction "2_2") (pintype "passive"))
      (node (ref "C71") (pin "2") (pinfunction "2_2") (pintype "passive"))
      (node (ref "C72") (pin "2") (pinfunction "2_2") (pintype "passive"))
      (node (ref "C73") (pin "2") (pinfunction "2_2") (pintype "passive"))
      (node (ref "C74") (pin "2") (pinfunction "2_2") (pintype "passive"))
      (node (ref "C75") (pin "2") (pinfunction "2_2") (pintype "passive"))
      (node (ref "C76") (pin "2") (pinfunction "2_2") (pintype "passive"))
      (node (ref "C77") (pin "2") (pinfunction "2_2") (pintype "passive"))
      (node (ref "C78") (pin "2") (pinfunction "2_2") (pintype "passive"))
      (node (ref "C79") (pin "2") (pinfunction "2_2") (pintype "passive"))
      (node (ref "C80") (pin "2") (pinfunction "2_2") (pintype "passive"))
      (node (ref "C81") (pin "2") (pinfunction "2_2") (pintype "passive"))
      (node (ref "C82") (pin "2") (pinfunction "2_2") (pintype "passive"))
      (node (ref "C83") (pin "2") (pinfunction "2_2") (pintype "passive"))
      (node (ref "C84") (pin "2") (pinfunction "2_2") (pintype "passive"))
      (node (ref "C85") (pin "2") (pinfunction "2_2") (pintype "passive"))
      (node (ref "C86") (pin "2") (pinfunction "2_2") (pintype "passive"))
      (node (ref "C87") (pin "2") (pinfunction "2_2") (pintype "passive"))
      (node (ref "C88") (pin "2") (pinfunction "2_2") (pintype "passive"))
      (node (ref "C89") (pin "2") (pinfunction "2_2") (pintype "passive"))
      (node (ref "C90") (pin "2") (pinfunction "2_2") (pintype "passive"))
      (node (ref "C91") (pin "2") (pinfunction "2_2") (pintype "passive"))
      (node (ref "C92") (pin "2") (pinfunction "2_2") (pintype "passive"))
      (node (ref "C93") (pin "2") (pinfunction "2_2") (pintype "passive"))
      (node (ref "C94") (pin "2") (pinfunction "2_2") (pintype "passive"))
      (node (ref "C95") (pin "2") (pinfunction "2_2") (pintype "passive"))
      (node (ref "C96") (pin "2") (pinfunction "2_2") (pintype "passive"))
      (node (ref "D49") (pin "1-VDD") (pinfunction "VDD_1-VDD") (pintype "power_in"))
      (node (ref "D50") (pin "1-VDD") (pinfunction "VDD_1-VDD") (pintype "power_in"))
      (node (ref "D51") (pin "1-VDD") (pinfunction "VDD_1-VDD") (pintype "power_in"))
      (node (ref "D52") (pin "1-VDD") (pinfunction "VDD_1-VDD") (pintype "power_in"))
      (node (ref "D53") (pin "1-VDD") (pinfunction "VDD_1-VDD") (pintype "power_in"))
      (node (ref "D54") (pin "1-VDD") (pinfunction "VDD_1-VDD") (pintype "power_in"))
      (node (ref "D55") (pin "1-VDD") (pinfunction "VDD_1-VDD") (pintype "power_in"))
      (node (ref "D56") (pin "1-VDD") (pinfunction "VDD_1-VDD") (pintype "power_in"))
      (node (ref "D57") (pin "1-VDD") (pinfunction "VDD_1-VDD") (pintype "power_in"))
      (node (ref "D58") (pin "1-VDD") (pinfunction "VDD_1-VDD") (pintype "power_in"))
      (node (ref "D59") (pin "1-VDD") (pinfunction "VDD_1-VDD") (pintype "power_in"))
      (node (ref "D60") (pin "1-VDD") (pinfunction "VDD_1-VDD") (pintype "power_in"))
      (node (ref "D61") (pin "1-VDD") (pinfunction "VDD_1-VDD") (pintype "power_in"))
      (node (ref "D62") (pin "1-VDD") (pinfunction "VDD_1-VDD") (pintype "power_in"))
      (node (ref "D63") (pin "1-VDD") (pinfunction "VDD_1-VDD") (pintype "power_in"))
      (node (ref "D64") (pin "1-VDD") (pinfunction "VDD_1-VDD") (pintype "power_in"))
      (node (ref "D65") (pin "1-VDD") (pinfunction "VDD_1-VDD") (pintype "power_in"))
      (node (ref "D66") (pin "1-VDD") (pinfunction "VDD_1-VDD") (pintype "power_in"))
      (node (ref "D67") (pin "1-VDD") (pinfunction "VDD_1-VDD") (pintype "power_in"))
      (node (ref "D68") (pin "1-VDD") (pinfunction "VDD_1-VDD") (pintype "power_in"))
      (node (ref "D69") (pin "1-VDD") (pinfunction "VDD_1-VDD") (pintype "power_in"))
      (node (ref "D70") (pin "1-VDD") (pinfunction "VDD_1-VDD") (pintype "power_in"))
      (node (ref "D71") (pin "1-VDD") (pinfunction "VDD_1-VDD") (pintype "power_in"))
      (node (ref "D72") (pin "1-VDD") (pinfunction "VDD_1-VDD") (pintype "power_in"))
      (node (ref "D73") (pin "1-VDD") (pinfunction "VDD_1-VDD") (pintype "power_in"))
      (node (ref "D74") (pin "1-VDD") (pinfunction "VDD_1-VDD") (pintype "power_in"))
      (node (ref "D75") (pin "1-VDD") (pinfunction "VDD_1-VDD") (pintype "power_in"))
      (node (ref "D76") (pin "1-VDD") (pinfunction "VDD_1-VDD") (pintype "power_in"))
      (node (ref "D77") (pin "1-VDD") (pinfunction "VDD_1-VDD") (pintype "power_in"))
      (node (ref "D78") (pin "1-VDD") (pinfunction "VDD_1-VDD") (pintype "power_in"))
      (node (ref "D79") (pin "1-VDD") (pinfunction "VDD_1-VDD") (pintype "power_in"))
      (node (ref "D80") (pin "1-VDD") (pinfunction "VDD_1-VDD") (pintype "power_in"))
      (node (ref "D81") (pin "1-VDD") (pinfunction "VDD_1-VDD") (pintype "power_in"))
      (node (ref "D82") (pin "1-VDD") (pinfunction "VDD_1-VDD") (pintype "power_in"))
      (node (ref "D83") (pin "1-VDD") (pinfunction "VDD_1-VDD") (pintype "power_in"))
      (node (ref "D84") (pin "1-VDD") (pinfunction "VDD_1-VDD") (pintype "power_in"))
      (node (ref "D85") (pin "1-VDD") (pinfunction "VDD_1-VDD") (pintype "power_in"))
      (node (ref "D86") (pin "1-VDD") (pinfunction "VDD_1-VDD") (pintype "power_in"))
      (node (ref "D87") (pin "1-VDD") (pinfunction "VDD_1-VDD") (pintype "power_in"))
      (node (ref "D88") (pin "1-VDD") (pinfunction "VDD_1-VDD") (pintype "power_in"))
      (node (ref "D89") (pin "1-VDD") (pinfunction "VDD_1-VDD") (pintype "power_in"))
      (node (ref "D90") (pin "1-VDD") (pinfunction "VDD_1-VDD") (pintype "power_in"))
      (node (ref "D91") (pin "1-VDD") (pinfunction "VDD_1-VDD") (pintype "power_in"))
      (node (ref "D92") (pin "1-VDD") (pinfunction "VDD_1-VDD") (pintype "power_in"))
      (node (ref "D93") (pin "1-VDD") (pinfunction "VDD_1-VDD") (pintype "power_in"))
      (node (ref "D94") (pin "1-VDD") (pinfunction "VDD_1-VDD") (pintype "power_in"))
      (node (ref "D95") (pin "1-VDD") (pinfunction "VDD_1-VDD") (pintype "power_in"))
      (node (ref "D96") (pin "1-VDD") (pinfunction "VDD_1-VDD") (pintype "power_in"))
    )
    (net (code "2") (name "/ROW_2_3") (class "Default")
      (node (ref "R3") (pin "2") (pinfunction "2_2") (pintype "passive"))
    )
    (net (code "3") (name "/ROW_4_5") (class "Default")
      (node (ref "D96") (pin "2-DOUT") (pinfunction "DO_2-DOUT") (pintype "output"))
    )
    (net (code "4") (name "/SIG2") (class "Default")
      (node (ref "R4") (pin "1") (pinfunction "1_1") (pintype "passive"))
    )
    (net (code "5") (name "GND") (class "Default")
      (node (ref "C49") (pin "1") (pinfunction "1_1") (pintype "passive"))
      (node (ref "C50") (pin "1") (pinfunction "1_1") (pintype "passive"))
      (node (ref "C51") (pin "1") (pinfunction "1_1") (pintype "passive"))
      (node (ref "C52") (pin "1") (pinfunction "1_1") (pintype "passive"))
      (node (ref "C53") (pin "1") (pinfunction "1_1") (pintype "passive"))
      (node (ref "C54") (pin "1") (pinfunction "1_1") (pintype "passive"))
      (node (ref "C55") (pin "1") (pinfunction "1_1") (pintype "passive"))
      (node (ref "C56") (pin "1") (pinfunction "1_1") (pintype "passive"))
      (node (ref "C57") (pin "1") (pinfunction "1_1") (pintype "passive"))
      (node (ref "C58") (pin "1") (pinfunction "1_1") (pintype "passive"))
      (node (ref "C59") (pin "1") (pinfunction "1_1") (pintype "passive"))
      (node (ref "C60") (pin "1") (pinfunction "1_1") (pintype "passive"))
      (node (ref "C61") (pin "1") (pinfunction "1_1") (pintype "passive"))
      (node (ref "C62") (pin "1") (pinfunction "1_1") (pintype "passive"))
      (node (ref "C63") (pin "1") (pinfunction "1_1") (pintype "passive"))
      (node (ref "C64") (pin "1") (pinfunction "1_1") (pintype "passive"))
      (node (ref "C65") (pin "1") (pinfunction "1_1") (pintype "passive"))
      (node (ref "C66") (pin "1") (pinfunction "1_1") (pintype "passive"))
      (node (ref "C67") (pin "1") (pinfunction "1_1") (pintype "passive"))
      (node (ref "C68") (pin "1") (pinfunction "1_1") (pintype "passive"))
      (node (ref "C69") (pin "1") (pinfunction "1_1") (pintype "passive"))
      (node (ref "C70") (pin "1") (pinfunction "1_1") (pintype "passive"))
      (node (ref "C71") (pin "1") (pinfunction "1_1") (pintype "passive"))
      (node (ref "C72") (pin "1") (pinfunction "1_1") (pintype "passive"))
      (node (ref "C73") (pin "1") (pinfunction "1_1") (pintype "passive"))
      (node (ref "C74") (pin "1") (pinfunction "1_1") (pintype "passive"))
      (node (ref "C75") (pin "1") (pinfunction "1_1") (pintype "passive"))
      (node (ref "C76") (pin "1") (pinfunction "1_1") (pintype "passive"))
      (node (ref "C77") (pin "1") (pinfunction "1_1") (pintype "passive"))
      (node (ref "C78") (pin "1") (pinfunction "1_1") (pintype "passive"))
      (node (ref "C79") (pin "1") (pinfunction "1_1") (pintype "passive"))
      (node (ref "C80") (pin "1") (pinfunction "1_1") (pintype "passive"))
      (node (ref "C81") (pin "1") (pinfunction "1_1") (pintype "passive"))
      (node (ref "C82") (pin "1") (pinfunction "1_1") (pintype "passive"))
      (node (ref "C83") (pin "1") (pinfunction "1_1") (pintype "passive"))
      (node (ref "C84") (pin "1") (pinfunction "1_1") (pintype "passive"))
      (node (ref "C85") (pin "1") (pinfunction "1_1") (pintype "passive"))
      (node (ref "C86") (pin "1") (pinfunction "1_1") (pintype "passive"))
      (node (ref "C87") (pin "1") (pinfunction "1_1") (pintype "passive"))
      (node (ref "C88") (pin "1") (pinfunction "1_1") (pintype "passive"))
      (node (ref "C89") (pin "1") (pinfunction "1_1") (pintype "passive"))
      (node (ref "C90") (pin "1") (pinfunction "1_1") (pintype "passive"))
      (node (ref "C91") (pin "1") (pinfunction "1_1") (pintype "passive"))
      (node (ref "C92") (pin "1") (pinfunction "1_1") (pintype "passive"))
      (node (ref "C93") (pin "1") (pinfunction "1_1") (pintype "passive"))
      (node (ref "C94") (pin "1") (pinfunction "1_1") (pintype "passive"))
      (node (ref "C95") (pin "1") (pinfunction "1_1") (pintype "passive"))
      (node (ref "C96") (pin "1") (pinfunction "1_1") (pintype "passive"))
      (node (ref "D49") (pin "3-GND") (pinfunction "GND_3-GND") (pintype "power_in"))
      (node (ref "D50") (pin "3-GND") (pinfunction "GND_3-GND") (pintype "power_in"))
      (node (ref "D51") (pin "3-GND") (pinfunction "GND_3-GND") (pintype "power_in"))
      (node (ref "D52") (pin "3-GND") (pinfunction "GND_3-GND") (pintype "power_in"))
      (node (ref "D53") (pin "3-GND") (pinfunction "GND_3-GND") (pintype "power_in"))
      (node (ref "D54") (pin "3-GND") (pinfunction "GND_3-GND") (pintype "power_in"))
      (node (ref "D55") (pin "3-GND") (pinfunction "GND_3-GND") (pintype "power_in"))
      (node (ref "D56") (pin "3-GND") (pinfunction "GND_3-GND") (pintype "power_in"))
      (node (ref "D57") (pin "3-GND") (pinfunction "GND_3-GND") (pintype "power_in"))
      (node (ref "D58") (pin "3-GND") (pinfunction "GND_3-GND") (pintype "power_in"))
      (node (ref "D59") (pin "3-GND") (pinfunction "GND_3-GND") (pintype "power_in"))
      (node (ref "D60") (pin "3-GND") (pinfunction "GND_3-GND") (pintype "power_in"))
      (node (ref "D61") (pin "3-GND") (pinfunction "GND_3-GND") (pintype "power_in"))
      (node (ref "D62") (pin "3-GND") (pinfunction "GND_3-GND") (pintype "power_in"))
      (node (ref "D63") (pin "3-GND") (pinfunction "GND_3-GND") (pintype "power_in"))
      (node (ref "D64") (pin "3-GND") (pinfunction "GND_3-GND") (pintype "power_in"))
      (node (ref "D65") (pin "3-GND") (pinfunction "GND_3-GND") (pintype "power_in"))
      (node (ref "D66") (pin "3-GND") (pinfunction "GND_3-GND") (pintype "power_in"))
      (node (ref "D67") (pin "3-GND") (pinfunction "GND_3-GND") (pintype "power_in"))
      (node (ref "D68") (pin "3-GND") (pinfunction "GND_3-GND") (pintype "power_in"))
      (node (ref "D69") (pin "3-GND") (pinfunction "GND_3-GND") (pintype "power_in"))
      (node (ref "D70") (pin "3-GND") (pinfunction "GND_3-GND") (pintype "power_in"))
      (node (ref "D71") (pin "3-GND") (pinfunction "GND_3-GND") (pintype "power_in"))
      (node (ref "D72") (pin "3-GND") (pinfunction "GND_3-GND") (pintype "power_in"))
      (node (ref "D73") (pin "3-GND") (pinfunction "GND_3-GND") (pintype "power_in"))
      (node (ref "D74") (pin "3-GND") (pinfunction "GND_3-GND") (pintype "power_in"))
      (node (ref "D75") (pin "3-GND") (pinfunction "GND_3-GND") (pintype "power_in"))
      (node (ref "D76") (pin "3-GND") (pinfunction "GND_3-GND") (pintype "power_in"))
      (node (ref "D77") (pin "3-GND") (pinfunction "GND_3-GND") (pintype "power_in"))
      (node (ref "D78") (pin "3-GND") (pinfunction "GND_3-GND") (pintype "power_in"))
      (node (ref "D79") (pin "3-GND") (pinfunction "GND_3-GND") (pintype "power_in"))
      (node (ref "D80") (pin "3-GND") (pinfunction "GND_3-GND") (pintype "power_in"))
      (node (ref "D81") (pin "3-GND") (pinfunction "GND_3-GND") (pintype "power_in"))
      (node (ref "D82") (pin "3-GND") (pinfunction "GND_3-GND") (pintype "power_in"))
      (node (ref "D83") (pin "3-GND") (pinfunction "GND_3-GND") (pintype "power_in"))
      (node (ref "D84") (pin "3-GND") (pinfunction "GND_3-GND") (pintype "power_in"))
      (node (ref "D85") (pin "3-GND") (pinfunction "GND_3-GND") (pintype "power_in"))
      (node (ref "D86") (pin "3-GND") (pinfunction "GND_3-GND") (pintype "power_in"))
      (node (ref "D87") (pin "3-GND") (pinfunction "GND_3-GND") (pintype "power_in"))
      (node (ref "D88") (pin "3-GND") (pinfunction "GND_3-GND") (pintype "power_in"))
      (node (ref "D89") (pin "3-GND") (pinfunction "GND_3-GND") (pintype "power_in"))
      (node (ref "D90") (pin "3-GND") (pinfunction "GND_3-GND") (pintype "power_in"))
      (node (ref "D91") (pin "3-GND") (pinfunction "GND_3-GND") (pintype "power_in"))
      (node (ref "D92") (pin "3-GND") (pinfunction "GND_3-GND") (pintype "power_in"))
      (node (ref "D93") (pin "3-GND") (pinfunction "GND_3-GND") (pintype "power_in"))
      (node (ref "D94") (pin "3-GND") (pinfunction "GND_3-GND") (pintype "power_in"))
      (node (ref "D95") (pin "3-GND") (pinfunction "GND_3-GND") (pintype "power_in"))
      (node (ref "D96") (pin "3-GND") (pinfunction "GND_3-GND") (pintype "power_in"))
    )
    (net (code "6") (name "Net-(D49-DI)") (class "Default")
      (node (ref "D49") (pin "4-DIN") (pinfunction "DI_4-DIN") (pintype "input"))
      (node (ref "R3") (pin "1") (pinfunction "1_1") (pintype "passive"))
      (node (ref "R4") (pin "2") (pinfunction "2_2") (pintype "passive"))
    )
    (net (code "7") (name "Net-(D49-DO)") (class "Default")
      (node (ref "D49") (pin "2-DOUT") (pinfunction "DO_2-DOUT") (pintype "output"))
      (node (ref "D50") (pin "4-DIN") (pinfunction "DI_4-DIN") (pintype "input"))
    )
    (net (code "8") (name "Net-(D50-DO)") (class "Default")
      (node (ref "D50") (pin "2-DOUT") (pinfunction "DO_2-DOUT") (pintype "output"))
      (node (ref "D51") (pin "4-DIN") (pinfunction "DI_4-DIN") (pintype "input"))
    )
    (net (code "9") (name "Net-(D51-DO)") (class "Default")
      (node (ref "D51") (pin "2-DOUT") (pinfunction "DO_2-DOUT") (pintype "output"))
      (node (ref "D52") (pin "4-DIN") (pinfunction "DI_4-DIN") (pintype "input"))
    )
    (net (code "10") (name "Net-(D52-DO)") (class "Default")
      (node (ref "D52") (pin "2-DOUT") (pinfunction "DO_2-DOUT") (pintype "output"))
      (node (ref "D53") (pin "4-DIN") (pinfunction "DI_4-DIN") (pintype "input"))
    )
    (net (code "11") (name "Net-(D53-DO)") (class "Default")
      (node (ref "D53") (pin "2-DOUT") (pinfunction "DO_2-DOUT") (pintype "output"))
      (node (ref "D54") (pin "4-DIN") (pinfunction "DI_4-DIN") (pintype "input"))
    )
    (net (code "12") (name "Net-(D54-DO)") (class "Default")
      (node (ref "D54") (pin "2-DOUT") (pinfunction "DO_2-DOUT") (pintype "output"))
      (node (ref "D55") (pin "4-DIN") (pinfunction "DI_4-DIN") (pintype "input"))
    )
    (net (code "13") (name "Net-(D55-DO)") (class "Default")
      (node (ref "D55") (pin "2-DOUT") (pinfunction "DO_2-DOUT") (pintype "output"))
      (node (ref "D56") (pin "4-DIN") (pinfunction "DI_4-DIN") (pintype "input"))
    )
    (net (code "14") (name "Net-(D56-DO)") (class "Default")
      (node (ref "D56") (pin "2-DOUT") (pinfunction "DO_2-DOUT") (pintype "output"))
      (node (ref "D57") (pin "4-DIN") (pinfunction "DI_4-DIN") (pintype "input"))
    )
    (net (code "15") (name "Net-(D57-DO)") (class "Default")
      (node (ref "D57") (pin "2-DOUT") (pinfunction "DO_2-DOUT") (pintype "output"))
      (node (ref "D58") (pin "4-DIN") (pinfunction "DI_4-DIN") (pintype "input"))
    )
    (net (code "16") (name "Net-(D58-DO)") (class "Default")
      (node (ref "D58") (pin "2-DOUT") (pinfunction "DO_2-DOUT") (pintype "output"))
      (node (ref "D59") (pin "4-DIN") (pinfunction "DI_4-DIN") (pintype "input"))
    )
    (net (code "17") (name "Net-(D59-DO)") (class "Default")
      (node (ref "D59") (pin "2-DOUT") (pinfunction "DO_2-DOUT") (pintype "output"))
      (node (ref "D60") (pin "4-DIN") (pinfunction "DI_4-DIN") (pintype "input"))
    )
    (net (code "18") (name "Net-(D60-DO)") (class "Default")
      (node (ref "D60") (pin "2-DOUT") (pinfunction "DO_2-DOUT") (pintype "output"))
      (node (ref "D61") (pin "4-DIN") (pinfunction "DI_4-DIN") (pintype "input"))
    )
    (net (code "19") (name "Net-(D61-DO)") (class "Default")
      (node (ref "D61") (pin "2-DOUT") (pinfunction "DO_2-DOUT") (pintype "output"))
      (node (ref "D62") (pin "4-DIN") (pinfunction "DI_4-DIN") (pintype "input"))
    )
    (net (code "20") (name "Net-(D62-DO)") (class "Default")
      (node (ref "D62") (pin "2-DOUT") (pinfunction "DO_2-DOUT") (pintype "output"))
      (node (ref "D63") (pin "4-DIN") (pinfunction "DI_4-DIN") (pintype "input"))
    )
    (net (code "21") (name "Net-(D63-DO)") (class "Default")
      (node (ref "D63") (pin "2-DOUT") (pinfunction "DO_2-DOUT") (pintype "output"))
      (node (ref "D64") (pin "4-DIN") (pinfunction "DI_4-DIN") (pintype "input"))
    )
    (net (code "22") (name "Net-(D64-DO)") (class "Default")
      (node (ref "D64") (pin "2-DOUT") (pinfunction "DO_2-DOUT") (pintype "output"))
      (node (ref "D65") (pin "4-DIN") (pinfunction "DI_4-DIN") (pintype "input"))
    )
    (net (code "23") (name "Net-(D65-DO)") (class "Default")
      (node (ref "D65") (pin "2-DOUT") (pinfunction "DO_2-DOUT") (pintype "output"))
      (node (ref "D66") (pin "4-DIN") (pinfunction "DI_4-DIN") (pintype "input"))
    )
    (net (code "24") (name "Net-(D66-DO)") (class "Default")
      (node (ref "D66") (pin "2-DOUT") (pinfunction "DO_2-DOUT") (pintype "output"))
      (node (ref "D67") (pin "4-DIN") (pinfunction "DI_4-DIN") (pintype "input"))
    )
    (net (code "25") (name "Net-(D67-DO)") (class "Default")
      (node (ref "D67") (pin "2-DOUT") (pinfunction "DO_2-DOUT") (pintype "output"))
      (node (ref "D68") (pin "4-DIN") (pinfunction "DI_4-DIN") (pintype "input"))
    )
    (net (code "26") (name "Net-(D68-DO)") (class "Default")
      (node (ref "D68") (pin "2-DOUT") (pinfunction "DO_2-DOUT") (pintype "output"))
      (node (ref "D69") (pin "4-DIN") (pinfunction "DI_4-DIN") (pintype "input"))
    )
    (net (code "27") (name "Net-(D69-DO)") (class "Default")
      (node (ref "D69") (pin "2-DOUT") (pinfunction "DO_2-DOUT") (pintype "output"))
      (node (ref "D70") (pin "4-DIN") (pinfunction "DI_4-DIN") (pintype "input"))
    )
    (net (code "28") (name "Net-(D70-DO)") (class "Default")
      (node (ref "D70") (pin "2-DOUT") (pinfunction "DO_2-DOUT") (pintype "output"))
      (node (ref "D71") (pin "4-DIN") (pinfunction "DI_4-DIN") (pintype "input"))
    )
    (net (code "29") (name "Net-(D71-DO)") (class "Default")
      (node (ref "D71") (pin "2-DOUT") (pinfunction "DO_2-DOUT") (pintype "output"))
      (node (ref "D72") (pin "4-DIN") (pinfunction "DI_4-DIN") (pintype "input"))
    )
    (net (code "30") (name "Net-(D72-DO)") (class "Default")
      (node (ref "D72") (pin "2-DOUT") (pinfunction "DO_2-DOUT") (pintype "output"))
      (node (ref "R5") (pin "2") (pinfunction "2_2") (pintype "passive"))
    )
    (net (code "31") (name "Net-(D73-DI)") (class "Default")
      (node (ref "D73") (pin "4-DIN") (pinfunction "DI_4-DIN") (pintype "input"))
      (node (ref "R5") (pin "1") (pinfunction "1_1") (pintype "passive"))
    )
    (net (code "32") (name "Net-(D73-DO)") (class "Default")
      (node (ref "D73") (pin "2-DOUT") (pinfunction "DO_2-DOUT") (pintype "output"))
      (node (ref "D74") (pin "4-DIN") (pinfunction "DI_4-DIN") (pintype "input"))
    )
    (net (code "33") (name "Net-(D74-DO)") (class "Default")
      (node (ref "D74") (pin "2-DOUT") (pinfunction "DO_2-DOUT") (pintype "output"))
      (node (ref "D75") (pin "4-DIN") (pinfunction "DI_4-DIN") (pintype "input"))
    )
    (net (code "34") (name "Net-(D75-DO)") (class "Default")
      (node (ref "D75") (pin "2-DOUT") (pinfunction "DO_2-DOUT") (pintype "output"))
      (node (ref "D76") (pin "4-DIN") (pinfunction "DI_4-DIN") (pintype "input"))
    )
    (net (code "35") (name "Net-(D76-DO)") (class "Default")
      (node (ref "D76") (pin "2-DOUT") (pinfunction "DO_2-DOUT") (pintype "output"))
      (node (ref "D77") (pin "4-DIN") (pinfunction "DI_4-DIN") (pintype "input"))
    )
    (net (code "36") (name "Net-(D77-DO)") (class "Default")
      (node (ref "D77") (pin "2-DOUT") (pinfunction "DO_2-DOUT") (pintype "output"))
      (node (ref "D78") (pin "4-DIN") (pinfunction "DI_4-DIN") (pintype "input"))
    )
    (net (code "37") (name "Net-(D78-DO)") (class "Default")
      (node (ref "D78") (pin "2-DOUT") (pinfunction "DO_2-DOUT") (pintype "output"))
      (node (ref "D79") (pin "4-DIN") (pinfunction "DI_4-DIN") (pintype "input"))
    )
    (net (code "38") (name "Net-(D79-DO)") (class "Default")
      (node (ref "D79") (pin "2-DOUT") (pinfunction "DO_2-DOUT") (pintype "output"))
      (node (ref "D80") (pin "4-DIN") (pinfunction "DI_4-DIN") (pintype "input"))
    )
    (net (code "39") (name "Net-(D80-DO)") (class "Default")
      (node (ref "D80") (pin "2-DOUT") (pinfunction "DO_2-DOUT") (pintype "output"))
      (node (ref "D81") (pin "4-DIN") (pinfunction "DI_4-DIN") (pintype "input"))
    )
    (net (code "40") (name "Net-(D81-DO)") (class "Default")
      (node (ref "D81") (pin "2-DOUT") (pinfunction "DO_2-DOUT") (pintype "output"))
      (node (ref "D82") (pin "4-DIN") (pinfunction "DI_4-DIN") (pintype "input"))
    )
    (net (code "41") (name "Net-(D82-DO)") (class "Default")
      (node (ref "D82") (pin "2-DOUT") (pinfunction "DO_2-DOUT") (pintype "output"))
      (node (ref "D83") (pin "4-DIN") (pinfunction "DI_4-DIN") (pintype "input"))
    )
    (net (code "42") (name "Net-(D83-DO)") (class "Default")
      (node (ref "D83") (pin "2-DOUT") (pinfunction "DO_2-DOUT") (pintype "output"))
      (node (ref "D84") (pin "4-DIN") (pinfunction "DI_4-DIN") (pintype "input"))
    )
    (net (code "43") (name "Net-(D84-DO)") (class "Default")
      (node (ref "D84") (pin "2-DOUT") (pinfunction "DO_2-DOUT") (pintype "output"))
      (node (ref "D85") (pin "4-DIN") (pinfunction "DI_4-DIN") (pintype "input"))
    )
    (net (code "44") (name "Net-(D85-DO)") (class "Default")
      (node (ref "D85") (pin "2-DOUT") (pinfunction "DO_2-DOUT") (pintype "output"))
      (node (ref "D86") (pin "4-DIN") (pinfunction "DI_4-DIN") (pintype "input"))
    )
    (net (code "45") (name "Net-(D86-DO)") (class "Default")
      (node (ref "D86") (pin "2-DOUT") (pinfunction "DO_2-DOUT") (pintype "output"))
      (node (ref "D87") (pin "4-DIN") (pinfunction "DI_4-DIN") (pintype "input"))
    )
    (net (code "46") (name "Net-(D87-DO)") (class "Default")
      (node (ref "D87") (pin "2-DOUT") (pinfunction "DO_2-DOUT") (pintype "output"))
      (node (ref "D88") (pin "4-DIN") (pinfunction "DI_4-DIN") (pintype "input"))
    )
    (net (code "47") (name "Net-(D88-DO)") (class "Default")
      (node (ref "D88") (pin "2-DOUT") (pinfunction "DO_2-DOUT") (pintype "output"))
      (node (ref "D89") (pin "4-DIN") (pinfunction "DI_4-DIN") (pintype "input"))
    )
    (net (code "48") (name "Net-(D89-DO)") (class "Default")
      (node (ref "D89") (pin "2-DOUT") (pinfunction "DO_2-DOUT") (pintype "output"))
      (node (ref "D90") (pin "4-DIN") (pinfunction "DI_4-DIN") (pintype "input"))
    )
    (net (code "49") (name "Net-(D90-DO)") (class "Default")
      (node (ref "D90") (pin "2-DOUT") (pinfunction "DO_2-DOUT") (pintype "output"))
      (node (ref "D91") (pin "4-DIN") (pinfunction "DI_4-DIN") (pintype "input"))
    )
    (net (code "50") (name "Net-(D91-DO)") (class "Default")
      (node (ref "D91") (pin "2-DOUT") (pinfunction "DO_2-DOUT") (pintype "output"))
      (node (ref "D92") (pin "4-DIN") (pinfunction "DI_4-DIN") (pintype "input"))
    )
    (net (code "51") (name "Net-(D92-DO)") (class "Default")
      (node (ref "D92") (pin "2-DOUT") (pinfunction "DO_2-DOUT") (pintype "output"))
      (node (ref "D93") (pin "4-DIN") (pinfunction "DI_4-DIN") (pintype "input"))
    )
    (net (code "52") (name "Net-(D93-DO)") (class "Default")
      (node (ref "D93") (pin "2-DOUT") (pinfunction "DO_2-DOUT") (pintype "output"))
      (node (ref "D94") (pin "4-DIN") (pinfunction "DI_4-DIN") (pintype "input"))
    )
    (net (code "53") (name "Net-(D94-DO)") (class "Default")
      (node (ref "D94") (pin "2-DOUT") (pinfunction "DO_2-DOUT") (pintype "output"))
      (node (ref "D95") (pin "4-DIN") (pinfunction "DI_4-DIN") (pintype "input"))
    )
    (net (code "54") (name "Net-(D95-DO)") (class "Default")
      (node (ref "D95") (pin "2-DOUT") (pinfunction "DO_2-DOUT") (pintype "output"))
      (node (ref "D96") (pin "4-DIN") (pinfunction "DI_4-DIN") (pintype "input"))
    )
  )
)
